# placa.net
KiCad netlist of a schematic drawn in EAGLE
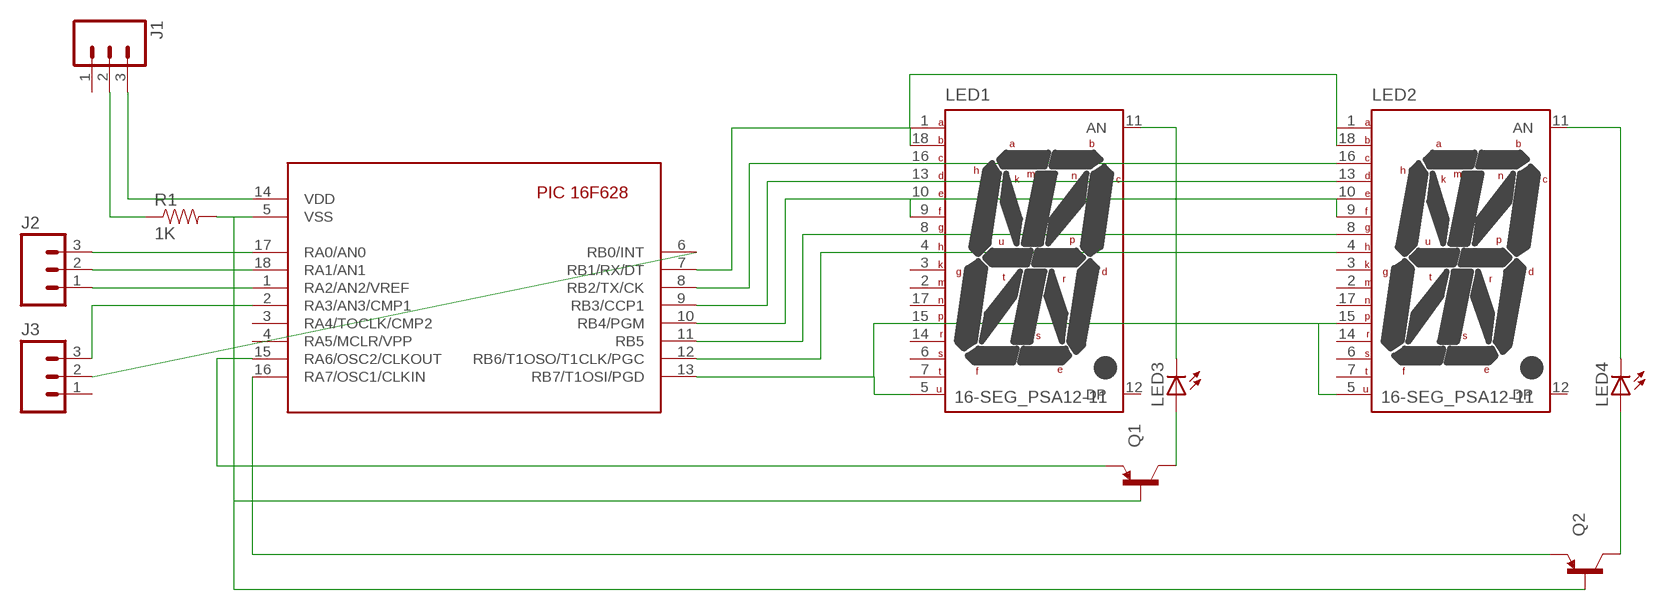
[diagram p0: schematic, sheet 1]

(export (version "E")
  (design (tool "Eeschema 10.0.6"))
  (components
    (comp (ref "J1")
      (value "M03-SCREW-5MM")
      (footprint "eagle-import:SCREWTERMINAL-5MM-3")
      (libsource (lib "eagle-import") (part "M03-SCREW-5MM"))
    )
    (comp (ref "J2")
      (value "M03-SCREW-5MM")
      (footprint "eagle-import:SCREWTERMINAL-5MM-3")
      (libsource (lib "eagle-import") (part "M03-SCREW-5MM"))
    )
    (comp (ref "J3")
      (value "M03-SCREW-5MM")
      (footprint "eagle-import:SCREWTERMINAL-5MM-3")
      (libsource (lib "eagle-import") (part "M03-SCREW-5MM"))
    )
    (comp (ref "LED1")
      (value "16-SEG_PSA12-11")
      (footprint "eagle-import:PSA12-11")
      (libsource (lib "eagle-import") (part "16-SEG_PSA12-11"))
    )
    (comp (ref "LED2")
      (value "16-SEG_PSA12-11")
      (footprint "eagle-import:PSA12-11")
      (libsource (lib "eagle-import") (part "16-SEG_PSA12-11"))
    )
    (comp (ref "LED3")
      (value "LED3MM")
      (footprint "eagle-import:LED3MM")
      (libsource (lib "eagle-import") (part "LED3MM"))
    )
    (comp (ref "LED4")
      (value "LED3MM")
      (footprint "eagle-import:LED3MM")
      (libsource (lib "eagle-import") (part "LED3MM"))
    )
    (comp (ref "Q1")
      (value "TRANSISTOR_PNPTO92")
      (footprint "eagle-import:TO-92")
      (libsource (lib "eagle-import") (part "TRANSISTOR_PNPTO92"))
    )
    (comp (ref "Q2")
      (value "TRANSISTOR_PNPTO92")
      (footprint "eagle-import:TO-92")
      (libsource (lib "eagle-import") (part "TRANSISTOR_PNPTO92"))
    )
    (comp (ref "R1")
      (value "1K")
      (footprint "eagle-import:AXIAL-0.3")
      (libsource (lib "eagle-import") (part "1KOHM-1/4W-1%(PTH)"))
    )
    (comp (ref "U$1")
      (value "16F628")
      (footprint "eagle-import:PIC16F628-18-LEAD-PDIP")
      (libsource (lib "eagle-import") (part "16F628"))
    )
  )
  (nets
    (net (code "1") (name "Net-(LED1-A)") (class "Default")
      (node (ref "LED1") (pin "1") (pinfunction "A_1") (pintype "passive"))
      (node (ref "LED1") (pin "18") (pinfunction "B_18") (pintype "passive"))
      (node (ref "LED2") (pin "1") (pinfunction "A_1") (pintype "passive"))
      (node (ref "LED2") (pin "18") (pinfunction "B_18") (pintype "passive"))
      (node (ref "U$1") (pin "7") (pinfunction "RB1/RX/DT_7") (pintype "bidirectional"))
    )
    (net (code "2") (name "Net-(LED1-AN)") (class "Default")
      (node (ref "LED1") (pin "11") (pinfunction "AN_11") (pintype "passive"))
      (node (ref "LED3") (pin "K") (pinfunction "C_K") (pintype "passive"))
    )
    (net (code "3") (name "Net-(LED1-C)") (class "Default")
      (node (ref "LED1") (pin "16") (pinfunction "C_16") (pintype "passive"))
      (node (ref "LED2") (pin "16") (pinfunction "C_16") (pintype "passive"))
      (node (ref "U$1") (pin "8") (pinfunction "RB2/TX/CK_8") (pintype "bidirectional"))
    )
    (net (code "4") (name "Net-(LED1-D)") (class "Default")
      (node (ref "LED1") (pin "13") (pinfunction "D_13") (pintype "passive"))
      (node (ref "LED2") (pin "13") (pinfunction "D_13") (pintype "passive"))
      (node (ref "U$1") (pin "9") (pinfunction "RB3/CCP1_9") (pintype "bidirectional"))
    )
    (net (code "5") (name "Net-(LED1-E)") (class "Default")
      (node (ref "LED1") (pin "10") (pinfunction "E_10") (pintype "passive"))
      (node (ref "LED1") (pin "9") (pinfunction "F_9") (pintype "passive"))
      (node (ref "LED2") (pin "10") (pinfunction "E_10") (pintype "passive"))
      (node (ref "LED2") (pin "9") (pinfunction "F_9") (pintype "passive"))
      (node (ref "U$1") (pin "10") (pinfunction "RB4/PGM_10") (pintype "bidirectional"))
    )
    (net (code "6") (name "Net-(LED1-G)") (class "Default")
      (node (ref "LED1") (pin "8") (pinfunction "G_8") (pintype "passive"))
      (node (ref "LED2") (pin "8") (pinfunction "G_8") (pintype "passive"))
      (node (ref "U$1") (pin "11") (pinfunction "RB5_11") (pintype "bidirectional"))
    )
    (net (code "7") (name "Net-(LED1-H)") (class "Default")
      (node (ref "LED1") (pin "4") (pinfunction "H_4") (pintype "passive"))
      (node (ref "LED2") (pin "4") (pinfunction "H_4") (pintype "passive"))
      (node (ref "U$1") (pin "12") (pinfunction "RB6/T1OSO/T1CLK/PGC_12") (pintype "bidirectional"))
    )
    (net (code "8") (name "Net-(LED1-P)") (class "Default")
      (node (ref "LED1") (pin "15") (pinfunction "P_15") (pintype "passive"))
      (node (ref "LED1") (pin "5") (pinfunction "U_5") (pintype "passive"))
      (node (ref "LED2") (pin "15") (pinfunction "P_15") (pintype "passive"))
      (node (ref "LED2") (pin "5") (pinfunction "U_5") (pintype "passive"))
      (node (ref "U$1") (pin "13") (pinfunction "RB7/T1OSI/PGD_13") (pintype "bidirectional"))
    )
    (net (code "9") (name "Net-(LED2-AN)") (class "Default")
      (node (ref "LED2") (pin "11") (pinfunction "AN_11") (pintype "passive"))
      (node (ref "LED4") (pin "K") (pinfunction "C_K") (pintype "passive"))
    )
    (net (code "10") (name "Net-(Q1-B)") (class "Default")
      (node (ref "Q1") (pin "2") (pinfunction "B_2") (pintype "passive"))
      (node (ref "Q2") (pin "2") (pinfunction "B_2") (pintype "passive"))
      (node (ref "R1") (pin "P$2") (pinfunction "2_P$2") (pintype "passive"))
      (node (ref "U$1") (pin "5") (pinfunction "VSS_5") (pintype "input"))
    )
    (net (code "11") (name "Net-(Q1-C)") (class "Default")
      (node (ref "LED3") (pin "A") (pinfunction "A_A") (pintype "passive"))
      (node (ref "Q1") (pin "3") (pinfunction "C_3") (pintype "passive"))
    )
    (net (code "12") (name "Net-(Q1-E)") (class "Default")
      (node (ref "Q1") (pin "1") (pinfunction "E_1") (pintype "passive"))
      (node (ref "U$1") (pin "15") (pinfunction "RA6/OSC2/CLKOUT_15") (pintype "bidirectional"))
    )
    (net (code "13") (name "Net-(Q2-C)") (class "Default")
      (node (ref "LED4") (pin "A") (pinfunction "A_A") (pintype "passive"))
      (node (ref "Q2") (pin "3") (pinfunction "C_3") (pintype "passive"))
    )
    (net (code "14") (name "Net-(Q2-E)") (class "Default")
      (node (ref "Q2") (pin "1") (pinfunction "E_1") (pintype "passive"))
      (node (ref "U$1") (pin "16") (pinfunction "RA7/OSC1/CLKIN_16") (pintype "bidirectional"))
    )
    (net (code "15") (name "Net-(R1-1)") (class "Default")
      (node (ref "J1") (pin "2") (pinfunction "2_2") (pintype "passive"))
      (node (ref "R1") (pin "P$1") (pinfunction "1_P$1") (pintype "passive"))
    )
    (net (code "16") (name "Net-(U$1-RA0{slash}AN0)") (class "Default")
      (node (ref "J2") (pin "3") (pinfunction "3_3") (pintype "passive"))
      (node (ref "U$1") (pin "17") (pinfunction "RA0/AN0_17") (pintype "bidirectional"))
    )
    (net (code "17") (name "Net-(U$1-RA1{slash}AN1)") (class "Default")
      (node (ref "J2") (pin "2") (pinfunction "2_2") (pintype "passive"))
      (node (ref "U$1") (pin "18") (pinfunction "RA1/AN1_18") (pintype "bidirectional"))
    )
    (net (code "18") (name "Net-(U$1-RA2{slash}AN2{slash}VREF)") (class "Default")
      (node (ref "J2") (pin "1") (pinfunction "1_1") (pintype "passive"))
      (node (ref "U$1") (pin "1") (pinfunction "RA2/AN2/VREF_1") (pintype "bidirectional"))
    )
    (net (code "19") (name "Net-(U$1-RA3{slash}AN3{slash}CMP1)") (class "Default")
      (node (ref "J3") (pin "3") (pinfunction "3_3") (pintype "passive"))
      (node (ref "U$1") (pin "2") (pinfunction "RA3/AN3/CMP1_2") (pintype "bidirectional"))
    )
    (net (code "20") (name "Net-(U$1-RB0{slash}INT)") (class "Default")
      (node (ref "J3") (pin "2") (pinfunction "2_2") (pintype "passive"))
      (node (ref "U$1") (pin "6") (pinfunction "RB0/INT_6") (pintype "bidirectional"))
    )
    (net (code "21") (name "Net-(U$1-VDD)") (class "Default")
      (node (ref "J1") (pin "3") (pinfunction "3_3") (pintype "passive"))
      (node (ref "U$1") (pin "14") (pinfunction "VDD_14") (pintype "input"))
    )
    (net (code "22") (name "unconnected-(J1-Pad1)") (class "Default")
      (node (ref "J1") (pin "1") (pinfunction "1_1") (pintype "passive"))
    )
    (net (code "23") (name "unconnected-(J3-Pad1)") (class "Default")
      (node (ref "J3") (pin "1") (pinfunction "1_1") (pintype "passive"))
    )
    (net (code "24") (name "unconnected-(LED1-DP-Pad12)") (class "Default")
      (node (ref "LED1") (pin "12") (pinfunction "DP_12") (pintype "passive"))
    )
    (net (code "25") (name "unconnected-(LED1-K-Pad3)") (class "Default")
      (node (ref "LED1") (pin "3") (pinfunction "K_3") (pintype "passive"))
    )
    (net (code "26") (name "unconnected-(LED1-M-Pad2)") (class "Default")
      (node (ref "LED1") (pin "2") (pinfunction "M_2") (pintype "passive"))
    )
    (net (code "27") (name "unconnected-(LED1-N-Pad17)") (class "Default")
      (node (ref "LED1") (pin "17") (pinfunction "N_17") (pintype "passive"))
    )
    (net (code "28") (name "unconnected-(LED1-R-Pad14)") (class "Default")
      (node (ref "LED1") (pin "14") (pinfunction "R_14") (pintype "passive"))
    )
    (net (code "29") (name "unconnected-(LED1-S-Pad6)") (class "Default")
      (node (ref "LED1") (pin "6") (pinfunction "S_6") (pintype "passive"))
    )
    (net (code "30") (name "unconnected-(LED1-T-Pad7)") (class "Default")
      (node (ref "LED1") (pin "7") (pinfunction "T_7") (pintype "passive"))
    )
    (net (code "31") (name "unconnected-(LED2-DP-Pad12)") (class "Default")
      (node (ref "LED2") (pin "12") (pinfunction "DP_12") (pintype "passive"))
    )
    (net (code "32") (name "unconnected-(LED2-K-Pad3)") (class "Default")
      (node (ref "LED2") (pin "3") (pinfunction "K_3") (pintype "passive"))
    )
    (net (code "33") (name "unconnected-(LED2-M-Pad2)") (class "Default")
      (node (ref "LED2") (pin "2") (pinfunction "M_2") (pintype "passive"))
    )
    (net (code "34") (name "unconnected-(LED2-N-Pad17)") (class "Default")
      (node (ref "LED2") (pin "17") (pinfunction "N_17") (pintype "passive"))
    )
    (net (code "35") (name "unconnected-(LED2-R-Pad14)") (class "Default")
      (node (ref "LED2") (pin "14") (pinfunction "R_14") (pintype "passive"))
    )
    (net (code "36") (name "unconnected-(LED2-S-Pad6)") (class "Default")
      (node (ref "LED2") (pin "6") (pinfunction "S_6") (pintype "passive"))
    )
    (net (code "37") (name "unconnected-(LED2-T-Pad7)") (class "Default")
      (node (ref "LED2") (pin "7") (pinfunction "T_7") (pintype "passive"))
    )
    (net (code "38") (name "unconnected-(U$1-RA4{slash}TOCLK{slash}CMP2-Pad3)") (class "Default")
      (node (ref "U$1") (pin "3") (pinfunction "RA4/TOCLK/CMP2_3") (pintype "bidirectional"))
    )
    (net (code "39") (name "unconnected-(U$1-RA5{slash}MCLR{slash}VPP-Pad4)") (class "Default")
      (node (ref "U$1") (pin "4") (pinfunction "RA5/MCLR/VPP_4") (pintype "bidirectional"))
    )
  )
)
